# DM1090FFC_TopLevel.net
KiCad netlist of a schematic drawn in Altium Designer
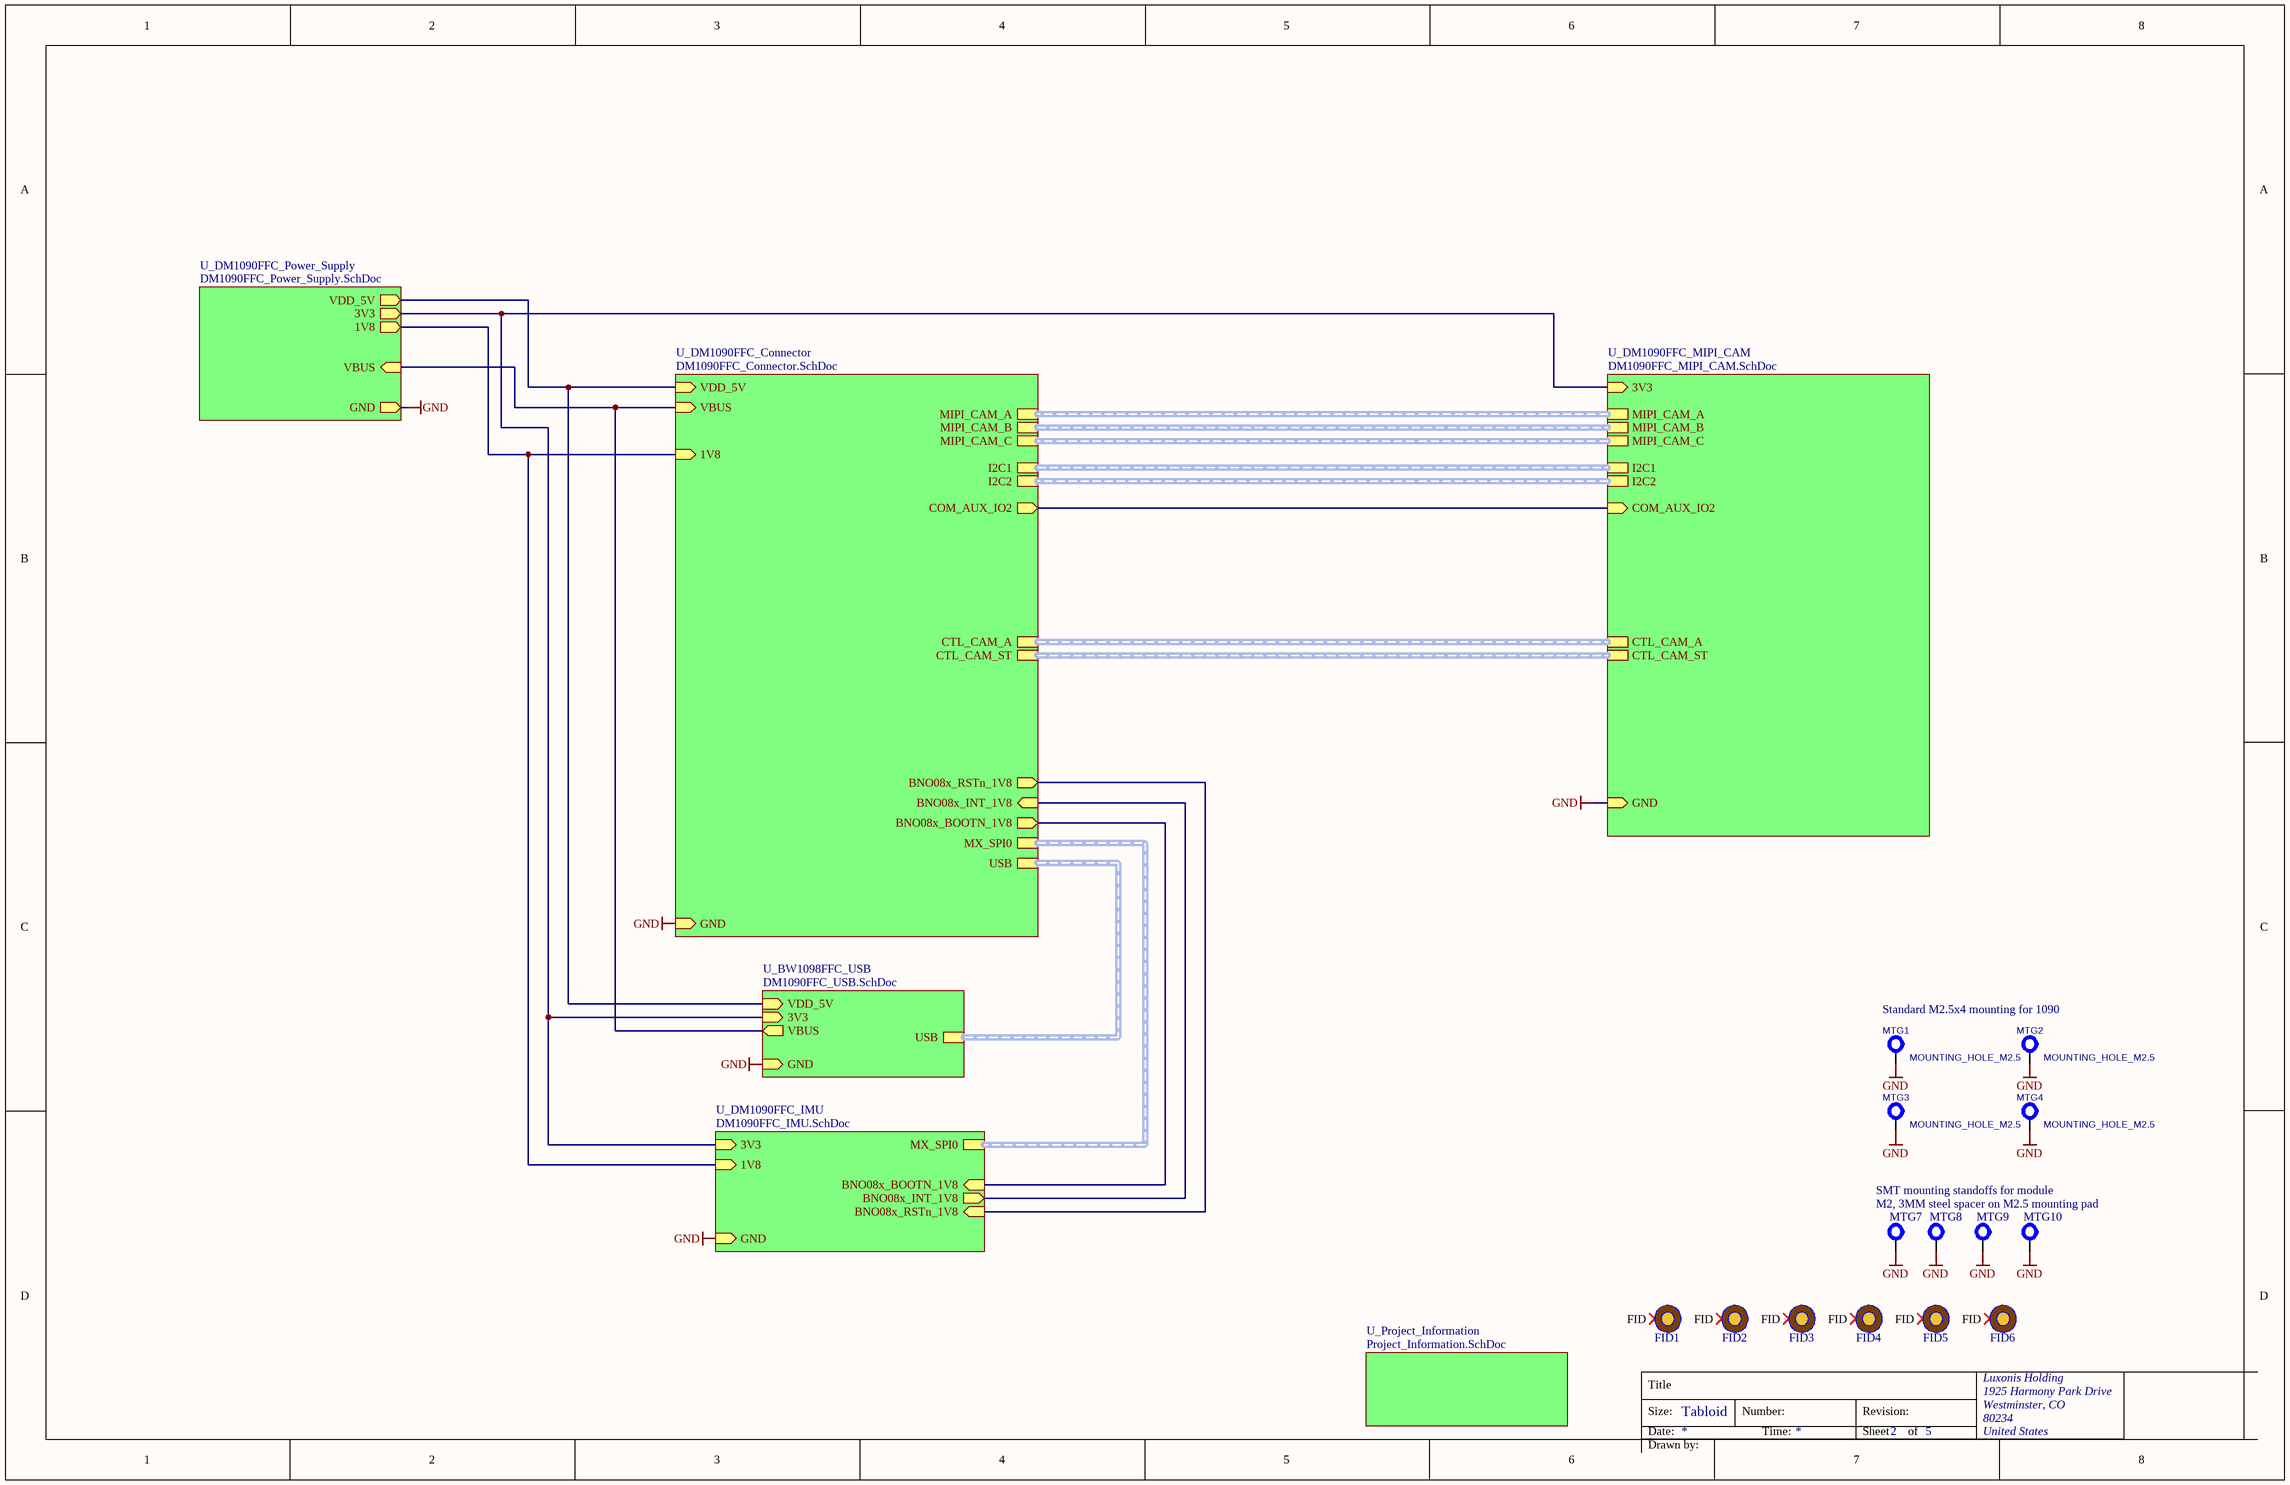
[diagram p0: DM1090FFC_TopLevel.SchDoc]

(export (version "E")
  (design (tool "Eeschema 10.0.6"))
  (components
    (comp (ref "FID1")
      (value "FIDUCIAL_ROUND_1MM")
      (footprint "LuxonisMaster:FIDUCIAL_ROUND_1MM")
      (description "Fiducial with various available footprints")
      (libsource (lib "LuxonisMaster") (part "FIDUCIAL"))
    )
    (comp (ref "FID2")
      (value "FIDUCIAL_ROUND_1MM")
      (footprint "LuxonisMaster:FIDUCIAL_ROUND_1MM")
      (description "Fiducial with various available footprints")
      (libsource (lib "LuxonisMaster") (part "FIDUCIAL"))
    )
    (comp (ref "FID3")
      (value "FIDUCIAL_ROUND_1MM")
      (footprint "LuxonisMaster:FIDUCIAL_ROUND_1MM")
      (description "Fiducial with various available footprints")
      (libsource (lib "LuxonisMaster") (part "FIDUCIAL"))
    )
    (comp (ref "FID4")
      (value "FIDUCIAL_ROUND_1MM")
      (footprint "LuxonisMaster:FIDUCIAL_ROUND_1MM")
      (description "Fiducial with various available footprints")
      (libsource (lib "LuxonisMaster") (part "FIDUCIAL"))
    )
    (comp (ref "FID5")
      (value "FIDUCIAL_ROUND_1MM")
      (footprint "LuxonisMaster:FIDUCIAL_ROUND_1MM")
      (description "Fiducial with various available footprints")
      (libsource (lib "LuxonisMaster") (part "FIDUCIAL"))
    )
    (comp (ref "FID6")
      (value "FIDUCIAL_ROUND_1MM")
      (footprint "LuxonisMaster:FIDUCIAL_ROUND_1MM")
      (description "Fiducial with various available footprints")
      (libsource (lib "LuxonisMaster") (part "FIDUCIAL"))
    )
    (comp (ref "MTG1")
      (value "MOUNTING_HOLE_M2.5")
      (footprint "LuxonisMaster:MOUNTING_HOLE_M2.5")
      (description "=CurrentFootprint")
      (libsource (lib "LuxonisMaster") (part "MP_Mounting-Holes"))
    )
    (comp (ref "MTG2")
      (value "MOUNTING_HOLE_M2.5")
      (footprint "LuxonisMaster:MOUNTING_HOLE_M2.5")
      (description "=CurrentFootprint")
      (libsource (lib "LuxonisMaster") (part "MP_Mounting-Holes"))
    )
    (comp (ref "MTG3")
      (value "MOUNTING_HOLE_M2.5")
      (footprint "LuxonisMaster:MOUNTING_HOLE_M2.5")
      (description "=CurrentFootprint")
      (libsource (lib "LuxonisMaster") (part "MP_Mounting-Holes"))
    )
    (comp (ref "MTG4")
      (value "MOUNTING_HOLE_M2.5")
      (footprint "LuxonisMaster:MOUNTING_HOLE_M2.5")
      (description "=CurrentFootprint")
      (libsource (lib "LuxonisMaster") (part "MP_Mounting-Holes"))
    )
    (comp (ref "MTG7")
      (value "M2, 3MM steel spacer on M2.5 mounting pad")
      (footprint "LuxonisMaster:9774030243R")
      (description "MP ROUND STANDOFF M2X0.4 STEEL 3MM")
      (libsource (lib "LuxonisMaster") (part "9774030243R"))
    )
    (comp (ref "MTG8")
      (value "M2, 3MM steel spacer on M2.5 mounting pad")
      (footprint "LuxonisMaster:9774030243R")
      (description "MP ROUND STANDOFF M2X0.4 STEEL 3MM")
      (libsource (lib "LuxonisMaster") (part "9774030243R"))
    )
    (comp (ref "MTG9")
      (value "M2, 3MM steel spacer on M2.5 mounting pad")
      (footprint "LuxonisMaster:9774030243R")
      (description "MP ROUND STANDOFF M2X0.4 STEEL 3MM")
      (libsource (lib "LuxonisMaster") (part "9774030243R"))
    )
    (comp (ref "MTG10")
      (value "M2, 3MM steel spacer on M2.5 mounting pad")
      (footprint "LuxonisMaster:9774030243R")
      (description "MP ROUND STANDOFF M2X0.4 STEEL 3MM")
      (libsource (lib "LuxonisMaster") (part "9774030243R"))
    )
  )
  (nets
    (net (code "18") (name "GND") (class "Default")
      (node (ref "MTG1") (pin "1") (pintype "passive"))
      (node (ref "MTG10") (pin "1") (pintype "passive"))
      (node (ref "MTG2") (pin "1") (pintype "passive"))
      (node (ref "MTG3") (pin "1") (pintype "passive"))
      (node (ref "MTG4") (pin "1") (pintype "passive"))
      (node (ref "MTG7") (pin "1") (pintype "passive"))
      (node (ref "MTG8") (pin "1") (pintype "passive"))
      (node (ref "MTG9") (pin "1") (pintype "passive"))
    )
    (net (code "19") (name "unconnected-(FID1-PadFID)") (class "Default")
      (node (ref "FID1") (pin "FID") (pinfunction "FID_FID") (pintype "input+no_connect"))
    )
    (net (code "20") (name "unconnected-(FID2-PadFID)") (class "Default")
      (node (ref "FID2") (pin "FID") (pinfunction "FID_FID") (pintype "input+no_connect"))
    )
    (net (code "21") (name "unconnected-(FID3-PadFID)") (class "Default")
      (node (ref "FID3") (pin "FID") (pinfunction "FID_FID") (pintype "input+no_connect"))
    )
    (net (code "22") (name "unconnected-(FID4-PadFID)") (class "Default")
      (node (ref "FID4") (pin "FID") (pinfunction "FID_FID") (pintype "input+no_connect"))
    )
    (net (code "23") (name "unconnected-(FID5-PadFID)") (class "Default")
      (node (ref "FID5") (pin "FID") (pinfunction "FID_FID") (pintype "input+no_connect"))
    )
    (net (code "24") (name "unconnected-(FID6-PadFID)") (class "Default")
      (node (ref "FID6") (pin "FID") (pinfunction "FID_FID") (pintype "input+no_connect"))
    )
  )
)
